# Single_Driver.net
KiCad netlist of a schematic drawn in EAGLE
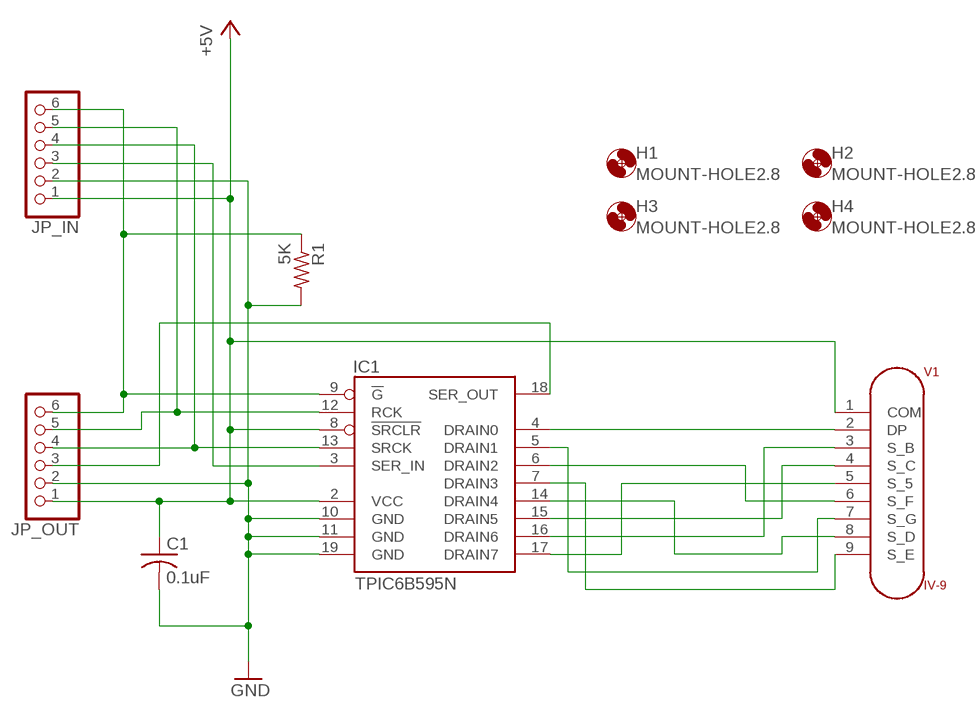
[diagram p0: schematic, sheet 1]

(export (version "E")
  (design (tool "Eeschema 10.0.6"))
  (components
    (comp (ref "C1")
      (value "0.1uF")
      (footprint "eagle-import:C025-025X050")
      (libsource (lib "eagle-import") (part "C-US025-025X050"))
    )
    (comp (ref "H1")
      (value "MOUNT-HOLE2.8")
      (footprint "eagle-import:2,8")
      (libsource (lib "eagle-import") (part "MOUNT-HOLE2.8"))
    )
    (comp (ref "H2")
      (value "MOUNT-HOLE2.8")
      (footprint "eagle-import:2,8")
      (libsource (lib "eagle-import") (part "MOUNT-HOLE2.8"))
    )
    (comp (ref "H3")
      (value "MOUNT-HOLE2.8")
      (footprint "eagle-import:2,8")
      (libsource (lib "eagle-import") (part "MOUNT-HOLE2.8"))
    )
    (comp (ref "H4")
      (value "MOUNT-HOLE2.8")
      (footprint "eagle-import:2,8")
      (libsource (lib "eagle-import") (part "MOUNT-HOLE2.8"))
    )
    (comp (ref "IC1")
      (value "TPIC6B595N")
      (footprint "eagle-import:DIL20")
      (libsource (lib "eagle-import") (part "TPIC6B595N"))
    )
    (comp (ref "JP_IN")
      (value "PINHD-1X6")
      (footprint "eagle-import:1X06")
      (libsource (lib "eagle-import") (part "PINHD-1X6"))
    )
    (comp (ref "JP_OUT")
      (value "PINHD-1X6")
      (footprint "eagle-import:1X06")
      (libsource (lib "eagle-import") (part "PINHD-1X6"))
    )
    (comp (ref "R1")
      (value "5K")
      (footprint "eagle-import:0207_9")
      (libsource (lib "eagle-import") (part "R-US_0207/9"))
    )
    (comp (ref "V1")
      (value "IV-9")
      (footprint "eagle-import:TO100")
      (libsource (lib "eagle-import") (part "IV-9"))
    )
  )
  (nets
    (net (code "1") (name "+5V") (class "Default")
      (node (ref "C1") (pin "1") (pinfunction "1_1") (pintype "passive"))
      (node (ref "IC1") (pin "2") (pinfunction "VCC_2") (pintype "power_in"))
      (node (ref "IC1") (pin "8") (pinfunction "~{SRCLR}_8") (pintype "input"))
      (node (ref "JP_IN") (pin "1") (pinfunction "1_1") (pintype "passive"))
      (node (ref "JP_OUT") (pin "1") (pinfunction "1_1") (pintype "passive"))
      (node (ref "V1") (pin "1") (pinfunction "COM_1") (pintype "bidirectional"))
    )
    (net (code "2") (name "GND") (class "Default")
      (node (ref "C1") (pin "2") (pinfunction "2_2") (pintype "passive"))
      (node (ref "IC1") (pin "10") (pinfunction "GND_10") (pintype "power_in"))
      (node (ref "IC1") (pin "11") (pinfunction "GND_11") (pintype "power_in"))
      (node (ref "IC1") (pin "19") (pinfunction "GND_19") (pintype "power_in"))
      (node (ref "JP_IN") (pin "2") (pinfunction "2_2") (pintype "passive"))
      (node (ref "JP_OUT") (pin "2") (pinfunction "2_2") (pintype "passive"))
      (node (ref "R1") (pin "2") (pinfunction "2_2") (pintype "passive"))
    )
    (net (code "3") (name "Net-(IC1-DRAIN0)") (class "Default")
      (node (ref "IC1") (pin "4") (pinfunction "DRAIN0_4") (pintype "open_collector"))
      (node (ref "V1") (pin "2") (pinfunction "DP_2") (pintype "bidirectional"))
    )
    (net (code "4") (name "Net-(IC1-DRAIN1)") (class "Default")
      (node (ref "IC1") (pin "5") (pinfunction "DRAIN1_5") (pintype "open_collector"))
      (node (ref "V1") (pin "7") (pinfunction "S_G_7") (pintype "bidirectional"))
    )
    (net (code "5") (name "Net-(IC1-DRAIN2)") (class "Default")
      (node (ref "IC1") (pin "6") (pinfunction "DRAIN2_6") (pintype "open_collector"))
      (node (ref "V1") (pin "6") (pinfunction "S_F_6") (pintype "bidirectional"))
    )
    (net (code "6") (name "Net-(IC1-DRAIN3)") (class "Default")
      (node (ref "IC1") (pin "7") (pinfunction "DRAIN3_7") (pintype "open_collector"))
      (node (ref "V1") (pin "9") (pinfunction "S_E_9") (pintype "bidirectional"))
    )
    (net (code "7") (name "Net-(IC1-DRAIN4)") (class "Default")
      (node (ref "IC1") (pin "14") (pinfunction "DRAIN4_14") (pintype "open_collector"))
      (node (ref "V1") (pin "8") (pinfunction "S_D_8") (pintype "bidirectional"))
    )
    (net (code "8") (name "Net-(IC1-DRAIN5)") (class "Default")
      (node (ref "IC1") (pin "15") (pinfunction "DRAIN5_15") (pintype "open_collector"))
      (node (ref "V1") (pin "4") (pinfunction "S_C_4") (pintype "bidirectional"))
    )
    (net (code "9") (name "Net-(IC1-DRAIN6)") (class "Default")
      (node (ref "IC1") (pin "16") (pinfunction "DRAIN6_16") (pintype "open_collector"))
      (node (ref "V1") (pin "3") (pinfunction "S_B_3") (pintype "bidirectional"))
    )
    (net (code "10") (name "Net-(IC1-DRAIN7)") (class "Default")
      (node (ref "IC1") (pin "17") (pinfunction "DRAIN7_17") (pintype "open_collector"))
      (node (ref "V1") (pin "5") (pinfunction "S_5_5") (pintype "bidirectional"))
    )
    (net (code "11") (name "Net-(IC1-RCK)") (class "Default")
      (node (ref "IC1") (pin "12") (pinfunction "RCK_12") (pintype "input"))
      (node (ref "JP_IN") (pin "5") (pinfunction "5_5") (pintype "passive"))
      (node (ref "JP_OUT") (pin "5") (pinfunction "5_5") (pintype "passive"))
    )
    (net (code "12") (name "Net-(IC1-SER_IN)") (class "Default")
      (node (ref "IC1") (pin "3") (pinfunction "SER_IN_3") (pintype "input"))
      (node (ref "JP_IN") (pin "3") (pinfunction "3_3") (pintype "passive"))
    )
    (net (code "13") (name "Net-(IC1-SER_OUT)") (class "Default")
      (node (ref "IC1") (pin "18") (pinfunction "SER_OUT_18") (pintype "output"))
      (node (ref "JP_OUT") (pin "3") (pinfunction "3_3") (pintype "passive"))
    )
    (net (code "14") (name "Net-(IC1-SRCK)") (class "Default")
      (node (ref "IC1") (pin "13") (pinfunction "SRCK_13") (pintype "input"))
      (node (ref "JP_IN") (pin "4") (pinfunction "4_4") (pintype "passive"))
      (node (ref "JP_OUT") (pin "4") (pinfunction "4_4") (pintype "passive"))
    )
    (net (code "15") (name "Net-(IC1-~{G})") (class "Default")
      (node (ref "IC1") (pin "9") (pinfunction "~{G}_9") (pintype "input"))
      (node (ref "JP_IN") (pin "6") (pinfunction "6_6") (pintype "passive"))
      (node (ref "JP_OUT") (pin "6") (pinfunction "6_6") (pintype "passive"))
      (node (ref "R1") (pin "1") (pinfunction "1_1") (pintype "passive"))
    )
  )
)
